# LTC3105_DoubleCharger.net
KiCad netlist of a schematic drawn in EAGLE
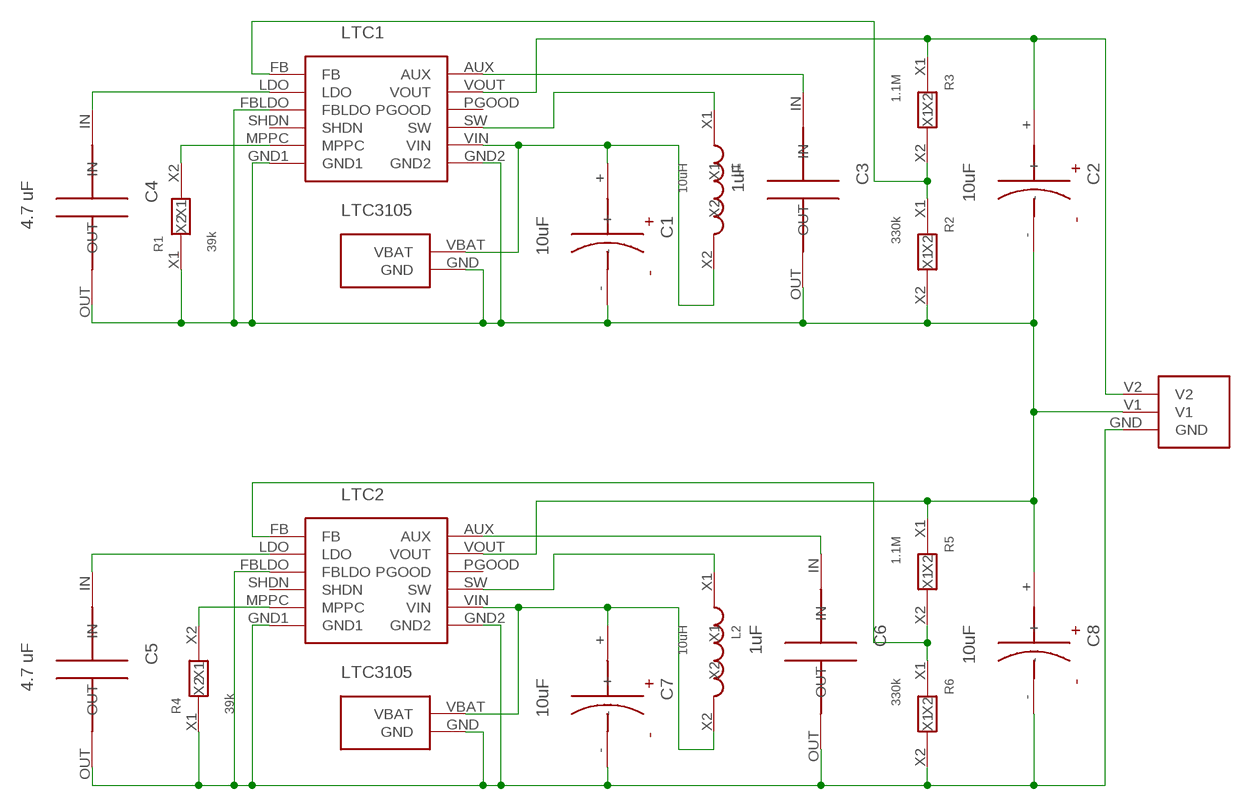
[diagram p0: schematic, sheet 1]

(export (version "E")
  (design (tool "Eeschema 10.0.6"))
  (components
    (comp (ref "C1")
      (value "10uF")
      (footprint "eagle-import:C_ELT_2MM")
      (libsource (lib "eagle-import") (part "C_ELT_2MM"))
    )
    (comp (ref "C2")
      (value "10uF")
      (footprint "eagle-import:C_ELT_2MM")
      (libsource (lib "eagle-import") (part "C_ELT_2MM"))
    )
    (comp (ref "C3")
      (value "1uF")
      (footprint "eagle-import:C_CER_5MM")
      (libsource (lib "eagle-import") (part "C_CER_5MM"))
    )
    (comp (ref "C4")
      (value "4.7 uF")
      (footprint "eagle-import:C_CER_5MM")
      (libsource (lib "eagle-import") (part "C_CER_5MM"))
    )
    (comp (ref "C5")
      (value "4.7 uF")
      (footprint "eagle-import:C_CER_5MM")
      (libsource (lib "eagle-import") (part "C_CER_5MM"))
    )
    (comp (ref "C6")
      (value "1uF")
      (footprint "eagle-import:C_CER_5MM")
      (libsource (lib "eagle-import") (part "C_CER_5MM"))
    )
    (comp (ref "C7")
      (value "10uF")
      (footprint "eagle-import:C_ELT_2MM")
      (libsource (lib "eagle-import") (part "C_ELT_2MM"))
    )
    (comp (ref "C8")
      (value "10uF")
      (footprint "eagle-import:C_ELT_2MM")
      (libsource (lib "eagle-import") (part "C_ELT_2MM"))
    )
    (comp (ref "L1")
      (value "10uH")
      (footprint "eagle-import:L_10X3")
      (libsource (lib "eagle-import") (part "L_10X3"))
    )
    (comp (ref "L2")
      (value "10uH")
      (footprint "eagle-import:L_10X3")
      (libsource (lib "eagle-import") (part "L_10X3"))
    )
    (comp (ref "LTC1")
      (value "LTC3105")
      (footprint "eagle-import:LTC3105")
      (libsource (lib "eagle-import") (part "LTC3105"))
    )
    (comp (ref "LTC2")
      (value "LTC3105")
      (footprint "eagle-import:LTC3105")
      (libsource (lib "eagle-import") (part "LTC3105"))
    )
    (comp (ref "R1")
      (value "39k")
      (footprint "eagle-import:R_6X2")
      (libsource (lib "eagle-import") (part "R_6X2"))
    )
    (comp (ref "R2")
      (value "330k")
      (footprint "eagle-import:R_6X2")
      (libsource (lib "eagle-import") (part "R_6X2"))
    )
    (comp (ref "R3")
      (value "1.1M")
      (footprint "eagle-import:R_6X2")
      (libsource (lib "eagle-import") (part "R_6X2"))
    )
    (comp (ref "R4")
      (value "39k")
      (footprint "eagle-import:R_6X2")
      (libsource (lib "eagle-import") (part "R_6X2"))
    )
    (comp (ref "R5")
      (value "1.1M")
      (footprint "eagle-import:R_6X2")
      (libsource (lib "eagle-import") (part "R_6X2"))
    )
    (comp (ref "R6")
      (value "330k")
      (footprint "eagle-import:R_6X2")
      (libsource (lib "eagle-import") (part "R_6X2"))
    )
    (comp (ref "U$1")
      (value "BAT3_PLUG")
      (footprint "eagle-import:BAT3_PLUG")
      (libsource (lib "eagle-import") (part "BAT3_PLUG"))
    )
    (comp (ref "U$3")
      (value "BAT_PLUG")
      (footprint "eagle-import:BAT_PLUG")
      (libsource (lib "eagle-import") (part "BAT_PLUG"))
    )
    (comp (ref "U$10")
      (value "BAT_PLUG")
      (footprint "eagle-import:BAT_PLUG")
      (libsource (lib "eagle-import") (part "BAT_PLUG"))
    )
  )
  (nets
    (net (code "1") (name "Net-(C1-Pad+)") (class "Default")
      (node (ref "C1") (pin "+") (pinfunction "+_+") (pintype "bidirectional"))
      (node (ref "L1") (pin "X2") (pinfunction "X2_X2") (pintype "bidirectional"))
      (node (ref "LTC1") (pin "VIN") (pinfunction "VIN_VIN") (pintype "bidirectional"))
      (node (ref "U$10") (pin "VBAT") (pinfunction "VBAT_VBAT") (pintype "bidirectional"))
    )
    (net (code "2") (name "Net-(C1-Pad-)") (class "Default")
      (node (ref "C1") (pin "-") (pinfunction "-_-") (pintype "bidirectional"))
      (node (ref "C2") (pin "-") (pinfunction "-_-") (pintype "bidirectional"))
      (node (ref "C3") (pin "OUT") (pinfunction "OUT_OUT") (pintype "bidirectional"))
      (node (ref "C4") (pin "OUT") (pinfunction "OUT_OUT") (pintype "bidirectional"))
      (node (ref "C8") (pin "+") (pinfunction "+_+") (pintype "bidirectional"))
      (node (ref "LTC1") (pin "FBLDO") (pinfunction "FBLDO_FBLDO") (pintype "bidirectional"))
      (node (ref "LTC1") (pin "GND1") (pinfunction "GND1_GND1") (pintype "bidirectional"))
      (node (ref "LTC1") (pin "GND2") (pinfunction "GND2_GND2") (pintype "bidirectional"))
      (node (ref "LTC2") (pin "VOUT") (pinfunction "VOUT_VOUT") (pintype "bidirectional"))
      (node (ref "R1") (pin "X1") (pinfunction "X1_X1") (pintype "bidirectional"))
      (node (ref "R2") (pin "X2") (pinfunction "X2_X2") (pintype "bidirectional"))
      (node (ref "R5") (pin "X1") (pinfunction "X1_X1") (pintype "bidirectional"))
      (node (ref "U$1") (pin "V1") (pinfunction "V1_V1") (pintype "bidirectional"))
      (node (ref "U$10") (pin "GND") (pinfunction "GND_GND") (pintype "bidirectional"))
    )
    (net (code "3") (name "Net-(C2-Pad+)") (class "Default")
      (node (ref "C2") (pin "+") (pinfunction "+_+") (pintype "bidirectional"))
      (node (ref "LTC1") (pin "VOUT") (pinfunction "VOUT_VOUT") (pintype "bidirectional"))
      (node (ref "R3") (pin "X1") (pinfunction "X1_X1") (pintype "bidirectional"))
      (node (ref "U$1") (pin "V2") (pinfunction "V2_V2") (pintype "bidirectional"))
    )
    (net (code "4") (name "Net-(C3-PadIN)") (class "Default")
      (node (ref "C3") (pin "IN") (pinfunction "IN_IN") (pintype "bidirectional"))
      (node (ref "LTC1") (pin "AUX") (pinfunction "AUX_AUX") (pintype "bidirectional"))
    )
    (net (code "5") (name "Net-(C4-PadIN)") (class "Default")
      (node (ref "C4") (pin "IN") (pinfunction "IN_IN") (pintype "bidirectional"))
      (node (ref "LTC1") (pin "LDO") (pinfunction "LDO_LDO") (pintype "bidirectional"))
    )
    (net (code "6") (name "Net-(C5-PadIN)") (class "Default")
      (node (ref "C5") (pin "IN") (pinfunction "IN_IN") (pintype "bidirectional"))
      (node (ref "LTC2") (pin "LDO") (pinfunction "LDO_LDO") (pintype "bidirectional"))
    )
    (net (code "7") (name "Net-(C5-PadOUT)") (class "Default")
      (node (ref "C5") (pin "OUT") (pinfunction "OUT_OUT") (pintype "bidirectional"))
      (node (ref "C6") (pin "OUT") (pinfunction "OUT_OUT") (pintype "bidirectional"))
      (node (ref "C7") (pin "-") (pinfunction "-_-") (pintype "bidirectional"))
      (node (ref "C8") (pin "-") (pinfunction "-_-") (pintype "bidirectional"))
      (node (ref "LTC2") (pin "FBLDO") (pinfunction "FBLDO_FBLDO") (pintype "bidirectional"))
      (node (ref "LTC2") (pin "GND1") (pinfunction "GND1_GND1") (pintype "bidirectional"))
      (node (ref "LTC2") (pin "GND2") (pinfunction "GND2_GND2") (pintype "bidirectional"))
      (node (ref "R4") (pin "X1") (pinfunction "X1_X1") (pintype "bidirectional"))
      (node (ref "R6") (pin "X2") (pinfunction "X2_X2") (pintype "bidirectional"))
      (node (ref "U$1") (pin "GND") (pinfunction "GND_GND") (pintype "bidirectional"))
      (node (ref "U$3") (pin "GND") (pinfunction "GND_GND") (pintype "bidirectional"))
    )
    (net (code "8") (name "Net-(C6-PadIN)") (class "Default")
      (node (ref "C6") (pin "IN") (pinfunction "IN_IN") (pintype "bidirectional"))
      (node (ref "LTC2") (pin "AUX") (pinfunction "AUX_AUX") (pintype "bidirectional"))
    )
    (net (code "9") (name "Net-(C7-Pad+)") (class "Default")
      (node (ref "C7") (pin "+") (pinfunction "+_+") (pintype "bidirectional"))
      (node (ref "L2") (pin "X2") (pinfunction "X2_X2") (pintype "bidirectional"))
      (node (ref "LTC2") (pin "VIN") (pinfunction "VIN_VIN") (pintype "bidirectional"))
      (node (ref "U$3") (pin "VBAT") (pinfunction "VBAT_VBAT") (pintype "bidirectional"))
    )
    (net (code "10") (name "Net-(L1-PadX1)") (class "Default")
      (node (ref "L1") (pin "X1") (pinfunction "X1_X1") (pintype "bidirectional"))
      (node (ref "LTC1") (pin "SW") (pinfunction "SW_SW") (pintype "bidirectional"))
    )
    (net (code "11") (name "Net-(L2-PadX1)") (class "Default")
      (node (ref "L2") (pin "X1") (pinfunction "X1_X1") (pintype "bidirectional"))
      (node (ref "LTC2") (pin "SW") (pinfunction "SW_SW") (pintype "bidirectional"))
    )
    (net (code "12") (name "Net-(LTC1-PadFB)") (class "Default")
      (node (ref "LTC1") (pin "FB") (pinfunction "FB_FB") (pintype "bidirectional"))
      (node (ref "R2") (pin "X1") (pinfunction "X1_X1") (pintype "bidirectional"))
      (node (ref "R3") (pin "X2") (pinfunction "X2_X2") (pintype "bidirectional"))
    )
    (net (code "13") (name "Net-(LTC1-PadMPPC)") (class "Default")
      (node (ref "LTC1") (pin "MPPC") (pinfunction "MPPC_MPPC") (pintype "bidirectional"))
      (node (ref "R1") (pin "X2") (pinfunction "X2_X2") (pintype "bidirectional"))
    )
    (net (code "14") (name "Net-(LTC2-PadFB)") (class "Default")
      (node (ref "LTC2") (pin "FB") (pinfunction "FB_FB") (pintype "bidirectional"))
      (node (ref "R5") (pin "X2") (pinfunction "X2_X2") (pintype "bidirectional"))
      (node (ref "R6") (pin "X1") (pinfunction "X1_X1") (pintype "bidirectional"))
    )
    (net (code "15") (name "Net-(LTC2-PadMPPC)") (class "Default")
      (node (ref "LTC2") (pin "MPPC") (pinfunction "MPPC_MPPC") (pintype "bidirectional"))
      (node (ref "R4") (pin "X2") (pinfunction "X2_X2") (pintype "bidirectional"))
    )
    (net (code "16") (name "unconnected-(LTC1-PadPGOOD)") (class "Default")
      (node (ref "LTC1") (pin "PGOOD") (pinfunction "PGOOD_PGOOD") (pintype "bidirectional"))
    )
    (net (code "17") (name "unconnected-(LTC1-PadSHDN)") (class "Default")
      (node (ref "LTC1") (pin "SHDN") (pinfunction "SHDN_SHDN") (pintype "bidirectional"))
    )
    (net (code "18") (name "unconnected-(LTC2-PadPGOOD)") (class "Default")
      (node (ref "LTC2") (pin "PGOOD") (pinfunction "PGOOD_PGOOD") (pintype "bidirectional"))
    )
    (net (code "19") (name "unconnected-(LTC2-PadSHDN)") (class "Default")
      (node (ref "LTC2") (pin "SHDN") (pinfunction "SHDN_SHDN") (pintype "bidirectional"))
    )
  )
)
